# Y_Stepper_Motor_Driver.net
KiCad netlist of a schematic drawn in Altium Designer
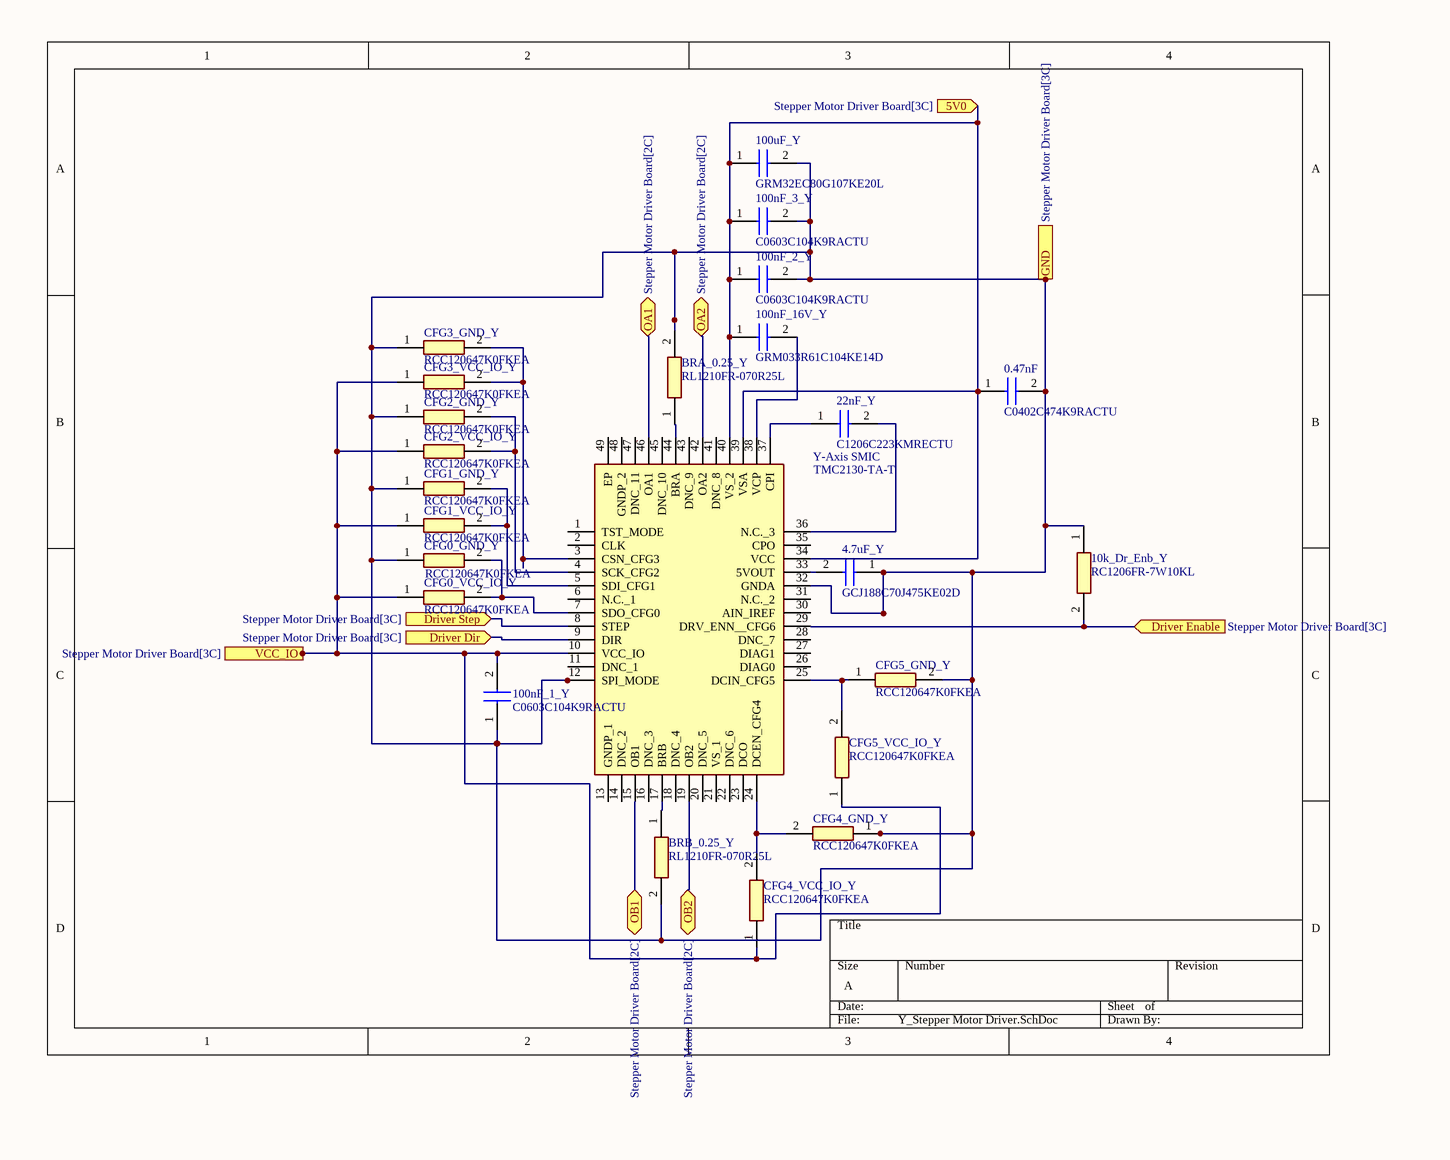
[diagram p0: Y_Stepper Motor Driver.SchDoc]

(export (version "E")
  (design (tool "Eeschema 10.0.6"))
  (components
    (comp (ref "0.47nF")
      (value "C0402C474K9RACTU")
      (footprint "SamacSys:CAPC1005X55N")
      (description "Capacitor")
      (fields (field (name "MOUSER PART NUMBER") "80-C0402C474K9RACTU"))
      (libsource (lib "*") (part "C0402C474K9RACTU"))
    )
    (comp (ref "4.7uF_Y")
      (value "GCJ188C70J475KE02D")
      (footprint "SamacSys:CAPC1608X100N")
      (description "Capacitor")
      (fields (field (name "MOUSER PART NUMBER") "81-GCJ188C70J475KE2D"))
      (libsource (lib "*") (part "GCJ188C70J475KE02D"))
    )
    (comp (ref "10k_Dr_Enb_Y")
      (value "RC1206FR-7W10KL")
      (footprint "SamacSys:RESC3116X65N")
      (description "Resistor")
      (libsource (lib "*") (part "RC1206FR-7W10KL"))
    )
    (comp (ref "22nF_Y")
      (value "C1206C223KMRECTU")
      (footprint "SamacSys:C1206")
      (description "Capacitor")
      (fields (field (name "MOUSER PART NUMBER") "80-C1206C223KMRECTU"))
      (libsource (lib "*") (part "C1206C223KMRECTU"))
    )
    (comp (ref "100nF_1_Y")
      (value "C0603C104K9RACTU")
      (footprint "SamacSys:C0603")
      (description "Capacitor")
      (fields (field (name "MOUSER PART NUMBER") "80-C0603C104K9R"))
      (libsource (lib "*") (part "C0603C104K9RACTU"))
    )
    (comp (ref "100nF_2_Y")
      (value "C0603C104K9RACTU")
      (footprint "SamacSys:C0603")
      (description "Capacitor")
      (fields (field (name "MOUSER PART NUMBER") "80-C0603C104K9R"))
      (libsource (lib "*") (part "C0603C104K9RACTU"))
    )
    (comp (ref "100nF_3_Y")
      (value "C0603C104K9RACTU")
      (footprint "SamacSys:C0603")
      (description "Capacitor")
      (fields (field (name "MOUSER PART NUMBER") "80-C0603C104K9R"))
      (libsource (lib "*") (part "C0603C104K9RACTU"))
    )
    (comp (ref "100nF_16V_Y")
      (value "GRM033R61C104KE14D")
      (footprint "SamacSys:CAPC0603X33N")
      (description "Capacitor")
      (fields (field (name "MOUSER PART NUMBER") "81-GRM033R61C104KE4D"))
      (libsource (lib "*") (part "GRM033R61C104KE14D"))
    )
    (comp (ref "100uF_Y")
      (value "GRM32EC80G107KE20L")
      (footprint "SamacSys:CAPC3225X270N")
      (description "Capacitor")
      (fields (field (name "MOUSER PART NUMBER") "81-GRM32EC80G107KE0L"))
      (libsource (lib "*") (part "GRM32EC80G107KE20L"))
    )
    (comp (ref "BRA_0.25_Y")
      (value "RL1210FR-070R25L")
      (footprint "SamacSys:RESC3126X65N")
      (description "Resistor")
      (fields (field (name "MOUSER PART NUMBER") "603-RL1210FR-070R25L"))
      (libsource (lib "*") (part "RL1210FR-070R25L"))
    )
    (comp (ref "BRB_0.25_Y")
      (value "RL1210FR-070R25L")
      (footprint "SamacSys:RESC3126X65N")
      (description "Resistor")
      (fields (field (name "MOUSER PART NUMBER") "603-RL1210FR-070R25L"))
      (libsource (lib "") (part "RL1210FR-070R25L_1"))
    )
    (comp (ref "CFG0_GND_Y")
      (value "RCC120647K0FKEA")
      (footprint "SamacSys:RCC1206_e3")
      (description "Resistor")
      (fields (field (name "MOUSER PART NUMBER") "71-RCC120647K0FKEA"))
      (libsource (lib "*") (part "RCC120647K0FKEA"))
    )
    (comp (ref "CFG0_VCC_IO_Y")
      (value "RCC120647K0FKEA")
      (footprint "SamacSys:RCC1206_e3")
      (description "Resistor")
      (fields (field (name "MOUSER PART NUMBER") "71-RCC120647K0FKEA"))
      (libsource (lib "*") (part "RCC120647K0FKEA"))
    )
    (comp (ref "CFG1_GND_Y")
      (value "RCC120647K0FKEA")
      (footprint "SamacSys:RCC1206_e3")
      (description "Resistor")
      (fields (field (name "MOUSER PART NUMBER") "71-RCC120647K0FKEA"))
      (libsource (lib "*") (part "RCC120647K0FKEA"))
    )
    (comp (ref "CFG1_VCC_IO_Y")
      (value "RCC120647K0FKEA")
      (footprint "SamacSys:RCC1206_e3")
      (description "Resistor")
      (fields (field (name "MOUSER PART NUMBER") "71-RCC120647K0FKEA"))
      (libsource (lib "*") (part "RCC120647K0FKEA"))
    )
    (comp (ref "CFG2_GND_Y")
      (value "RCC120647K0FKEA")
      (footprint "SamacSys:RCC1206_e3")
      (description "Resistor")
      (fields (field (name "MOUSER PART NUMBER") "71-RCC120647K0FKEA"))
      (libsource (lib "*") (part "RCC120647K0FKEA"))
    )
    (comp (ref "CFG2_VCC_IO_Y")
      (value "RCC120647K0FKEA")
      (footprint "SamacSys:RCC1206_e3")
      (description "Resistor")
      (fields (field (name "MOUSER PART NUMBER") "71-RCC120647K0FKEA"))
      (libsource (lib "*") (part "RCC120647K0FKEA"))
    )
    (comp (ref "CFG3_GND_Y")
      (value "RCC120647K0FKEA")
      (footprint "SamacSys:RCC1206_e3")
      (description "Resistor")
      (fields (field (name "MOUSER PART NUMBER") "71-RCC120647K0FKEA"))
      (libsource (lib "*") (part "RCC120647K0FKEA"))
    )
    (comp (ref "CFG3_VCC_IO_Y")
      (value "RCC120647K0FKEA")
      (footprint "SamacSys:RCC1206_e3")
      (description "Resistor")
      (fields (field (name "MOUSER PART NUMBER") "71-RCC120647K0FKEA"))
      (libsource (lib "*") (part "RCC120647K0FKEA"))
    )
    (comp (ref "CFG4_GND_Y")
      (value "RCC120647K0FKEA")
      (footprint "SamacSys:RCC1206_e3")
      (description "Resistor")
      (fields (field (name "MOUSER PART NUMBER") "71-RCC120647K0FKEA"))
      (libsource (lib "") (part "RCC120647K0FKEA_2"))
    )
    (comp (ref "CFG4_VCC_IO_Y")
      (value "RCC120647K0FKEA")
      (footprint "SamacSys:RCC1206_e3")
      (description "Resistor")
      (fields (field (name "MOUSER PART NUMBER") "71-RCC120647K0FKEA"))
      (libsource (lib "") (part "RCC120647K0FKEA_1"))
    )
    (comp (ref "CFG5_GND_Y")
      (value "RCC120647K0FKEA")
      (footprint "SamacSys:RCC1206_e3")
      (description "Resistor")
      (fields (field (name "MOUSER PART NUMBER") "71-RCC120647K0FKEA"))
      (libsource (lib "*") (part "RCC120647K0FKEA"))
    )
    (comp (ref "CFG5_VCC_IO_Y")
      (value "RCC120647K0FKEA")
      (footprint "SamacSys:RCC1206_e3")
      (description "Resistor")
      (fields (field (name "MOUSER PART NUMBER") "71-RCC120647K0FKEA"))
      (libsource (lib "") (part "RCC120647K0FKEA_1"))
    )
    (comp (ref "Y-Axis SMIC")
      (value "TMC2130-TA-T")
      (footprint "SamacSys:QFP50P900X900X120-49N")
      (description "Integrated Circuit")
      (fields (field (name "MOUSER PART NUMBER") "700-TMC2130-TA-T"))
      (libsource (lib "*") (part "TMC2130-TA-T"))
    )
  )
  (nets
    (net (code "1") (name "/5V0") (class "Default")
      (node (ref "0.47nF") (pin "1") (pinfunction "1_1") (pintype "passive"))
      (node (ref "100nF_16V_Y") (pin "1") (pinfunction "1_1") (pintype "passive"))
      (node (ref "100nF_2_Y") (pin "1") (pinfunction "1_1") (pintype "passive"))
      (node (ref "100nF_3_Y") (pin "1") (pinfunction "1_1") (pintype "passive"))
      (node (ref "100uF_Y") (pin "1") (pinfunction "1_1") (pintype "passive"))
      (node (ref "Y-Axis SMIC") (pin "34") (pinfunction "VCC_34") (pintype "passive"))
      (node (ref "Y-Axis SMIC") (pin "39") (pinfunction "VSA_39") (pintype "passive"))
      (node (ref "Y-Axis SMIC") (pin "40") (pinfunction "VS_2_40") (pintype "passive"))
    )
    (net (code "2") (name "/Driver Dir") (class "Default")
      (node (ref "Y-Axis SMIC") (pin "9") (pinfunction "DIR_9") (pintype "passive"))
    )
    (net (code "3") (name "/Driver Enable") (class "Default")
      (node (ref "10k_Dr_Enb_Y") (pin "2") (pinfunction "2_2") (pintype "passive"))
      (node (ref "Y-Axis SMIC") (pin "29") (pinfunction "DRV_ENN__CFG6_29") (pintype "passive"))
    )
    (net (code "4") (name "/Driver Step") (class "Default")
      (node (ref "Y-Axis SMIC") (pin "8") (pinfunction "STEP_8") (pintype "passive"))
    )
    (net (code "5") (name "/GND") (class "Default")
      (node (ref "0.47nF") (pin "2") (pinfunction "2_2") (pintype "passive"))
      (node (ref "100nF_1_Y") (pin "1") (pinfunction "1_1") (pintype "passive"))
      (node (ref "100nF_2_Y") (pin "2") (pinfunction "2_2") (pintype "passive"))
      (node (ref "100nF_3_Y") (pin "2") (pinfunction "2_2") (pintype "passive"))
      (node (ref "100uF_Y") (pin "2") (pinfunction "2_2") (pintype "passive"))
      (node (ref "10k_Dr_Enb_Y") (pin "1") (pinfunction "1_1") (pintype "passive"))
      (node (ref "4.7uF_Y") (pin "1") (pinfunction "1_1") (pintype "passive"))
      (node (ref "BRA_0.25_Y") (pin "2") (pinfunction "2_2") (pintype "passive"))
      (node (ref "BRB_0.25_Y") (pin "2") (pinfunction "2_2") (pintype "passive"))
      (node (ref "CFG0_GND_Y") (pin "1") (pinfunction "1_1") (pintype "passive"))
      (node (ref "CFG1_GND_Y") (pin "1") (pinfunction "1_1") (pintype "passive"))
      (node (ref "CFG2_GND_Y") (pin "1") (pinfunction "1_1") (pintype "passive"))
      (node (ref "CFG3_GND_Y") (pin "1") (pinfunction "1_1") (pintype "passive"))
      (node (ref "CFG4_GND_Y") (pin "1") (pinfunction "1_1") (pintype "passive"))
      (node (ref "CFG5_GND_Y") (pin "2") (pinfunction "2_2") (pintype "passive"))
      (node (ref "Y-Axis SMIC") (pin "12") (pinfunction "SPI_MODE_12") (pintype "passive"))
      (node (ref "Y-Axis SMIC") (pin "32") (pinfunction "GNDA_32") (pintype "passive"))
    )
    (net (code "6") (name "/OA1") (class "Default")
      (node (ref "Y-Axis SMIC") (pin "46") (pinfunction "OA1_46") (pintype "passive"))
    )
    (net (code "7") (name "/OA2") (class "Default")
      (node (ref "Y-Axis SMIC") (pin "42") (pinfunction "OA2_42") (pintype "passive"))
    )
    (net (code "8") (name "/OB1") (class "Default")
      (node (ref "Y-Axis SMIC") (pin "15") (pinfunction "OB1_15") (pintype "passive"))
    )
    (net (code "9") (name "/OB2") (class "Default")
      (node (ref "Y-Axis SMIC") (pin "19") (pinfunction "OB2_19") (pintype "passive"))
    )
    (net (code "10") (name "/VCC_IO") (class "Default")
      (node (ref "100nF_1_Y") (pin "2") (pinfunction "2_2") (pintype "passive"))
      (node (ref "CFG0_VCC_IO_Y") (pin "1") (pinfunction "1_1") (pintype "passive"))
      (node (ref "CFG1_VCC_IO_Y") (pin "1") (pinfunction "1_1") (pintype "passive"))
      (node (ref "CFG2_VCC_IO_Y") (pin "1") (pinfunction "1_1") (pintype "passive"))
      (node (ref "CFG3_VCC_IO_Y") (pin "1") (pinfunction "1_1") (pintype "passive"))
      (node (ref "CFG4_VCC_IO_Y") (pin "1") (pinfunction "1_1") (pintype "passive"))
      (node (ref "CFG5_VCC_IO_Y") (pin "1") (pinfunction "1_1") (pintype "passive"))
      (node (ref "Y-Axis SMIC") (pin "10") (pinfunction "VCC_IO_10") (pintype "passive"))
    )
    (net (code "11") (name "Net-(Y-Axis SMIC-5VOUT)") (class "Default")
      (node (ref "4.7uF_Y") (pin "2") (pinfunction "2_2") (pintype "passive"))
      (node (ref "Y-Axis SMIC") (pin "33") (pinfunction "5VOUT_33") (pintype "passive"))
    )
    (net (code "12") (name "Net-(Y-Axis SMIC-BRA)") (class "Default")
      (node (ref "BRA_0.25_Y") (pin "1") (pinfunction "1_1") (pintype "passive"))
      (node (ref "Y-Axis SMIC") (pin "44") (pinfunction "BRA_44") (pintype "passive"))
    )
    (net (code "13") (name "Net-(Y-Axis SMIC-BRB)") (class "Default")
      (node (ref "BRB_0.25_Y") (pin "1") (pinfunction "1_1") (pintype "passive"))
      (node (ref "Y-Axis SMIC") (pin "17") (pinfunction "BRB_17") (pintype "passive"))
    )
    (net (code "14") (name "Net-(Y-Axis SMIC-CPI)") (class "Default")
      (node (ref "22nF_Y") (pin "1") (pinfunction "1_1") (pintype "passive"))
      (node (ref "Y-Axis SMIC") (pin "37") (pinfunction "CPI_37") (pintype "passive"))
    )
    (net (code "15") (name "Net-(Y-Axis SMIC-CSN_CFG3)") (class "Default")
      (node (ref "CFG3_GND_Y") (pin "2") (pinfunction "2_2") (pintype "passive"))
      (node (ref "CFG3_VCC_IO_Y") (pin "2") (pinfunction "2_2") (pintype "passive"))
      (node (ref "Y-Axis SMIC") (pin "3") (pinfunction "CSN_CFG3_3") (pintype "passive"))
    )
    (net (code "16") (name "Net-(Y-Axis SMIC-DCEN_CFG4)") (class "Default")
      (node (ref "CFG4_GND_Y") (pin "2") (pinfunction "2_2") (pintype "passive"))
      (node (ref "CFG4_VCC_IO_Y") (pin "2") (pinfunction "2_2") (pintype "passive"))
      (node (ref "Y-Axis SMIC") (pin "24") (pinfunction "DCEN_CFG4_24") (pintype "passive"))
    )
    (net (code "17") (name "Net-(Y-Axis SMIC-DCIN_CFG5)") (class "Default")
      (node (ref "CFG5_GND_Y") (pin "1") (pinfunction "1_1") (pintype "passive"))
      (node (ref "CFG5_VCC_IO_Y") (pin "2") (pinfunction "2_2") (pintype "passive"))
      (node (ref "Y-Axis SMIC") (pin "25") (pinfunction "DCIN_CFG5_25") (pintype "passive"))
    )
    (net (code "18") (name "Net-(Y-Axis SMIC-N.C._3)") (class "Default")
      (node (ref "22nF_Y") (pin "2") (pinfunction "2_2") (pintype "passive"))
      (node (ref "Y-Axis SMIC") (pin "36") (pinfunction "N.C._3_36") (pintype "passive"))
    )
    (net (code "19") (name "Net-(Y-Axis SMIC-SCK_CFG2)") (class "Default")
      (node (ref "CFG2_GND_Y") (pin "2") (pinfunction "2_2") (pintype "passive"))
      (node (ref "CFG2_VCC_IO_Y") (pin "2") (pinfunction "2_2") (pintype "passive"))
      (node (ref "Y-Axis SMIC") (pin "4") (pinfunction "SCK_CFG2_4") (pintype "passive"))
    )
    (net (code "20") (name "Net-(Y-Axis SMIC-SDI_CFG1)") (class "Default")
      (node (ref "CFG1_GND_Y") (pin "2") (pinfunction "2_2") (pintype "passive"))
      (node (ref "CFG1_VCC_IO_Y") (pin "2") (pinfunction "2_2") (pintype "passive"))
      (node (ref "Y-Axis SMIC") (pin "5") (pinfunction "SDI_CFG1_5") (pintype "passive"))
    )
    (net (code "21") (name "Net-(Y-Axis SMIC-SDO_CFG0)") (class "Default")
      (node (ref "CFG0_GND_Y") (pin "2") (pinfunction "2_2") (pintype "passive"))
      (node (ref "CFG0_VCC_IO_Y") (pin "2") (pinfunction "2_2") (pintype "passive"))
      (node (ref "Y-Axis SMIC") (pin "7") (pinfunction "SDO_CFG0_7") (pintype "passive"))
    )
    (net (code "22") (name "Net-(Y-Axis SMIC-VCP)") (class "Default")
      (node (ref "100nF_16V_Y") (pin "2") (pinfunction "2_2") (pintype "passive"))
      (node (ref "Y-Axis SMIC") (pin "38") (pinfunction "VCP_38") (pintype "passive"))
    )
    (net (code "23") (name "unconnected-(Y-Axis SMIC-AIN_IREF-Pad30)") (class "Default")
      (node (ref "Y-Axis SMIC") (pin "30") (pinfunction "AIN_IREF_30") (pintype "passive"))
    )
    (net (code "24") (name "unconnected-(Y-Axis SMIC-CLK-Pad2)") (class "Default")
      (node (ref "Y-Axis SMIC") (pin "2") (pinfunction "CLK_2") (pintype "passive"))
    )
    (net (code "25") (name "unconnected-(Y-Axis SMIC-CPO-Pad35)") (class "Default")
      (node (ref "Y-Axis SMIC") (pin "35") (pinfunction "CPO_35") (pintype "passive"))
    )
    (net (code "26") (name "unconnected-(Y-Axis SMIC-DCO-Pad23)") (class "Default")
      (node (ref "Y-Axis SMIC") (pin "23") (pinfunction "DCO_23") (pintype "passive"))
    )
    (net (code "27") (name "unconnected-(Y-Axis SMIC-DIAG0-Pad26)") (class "Default")
      (node (ref "Y-Axis SMIC") (pin "26") (pinfunction "DIAG0_26") (pintype "passive"))
    )
    (net (code "28") (name "unconnected-(Y-Axis SMIC-DIAG1-Pad27)") (class "Default")
      (node (ref "Y-Axis SMIC") (pin "27") (pinfunction "DIAG1_27") (pintype "passive"))
    )
    (net (code "29") (name "unconnected-(Y-Axis SMIC-DNC_1-Pad11)") (class "Default")
      (node (ref "Y-Axis SMIC") (pin "11") (pinfunction "DNC_1_11") (pintype "passive"))
    )
    (net (code "30") (name "unconnected-(Y-Axis SMIC-DNC_2-Pad14)") (class "Default")
      (node (ref "Y-Axis SMIC") (pin "14") (pinfunction "DNC_2_14") (pintype "passive"))
    )
    (net (code "31") (name "unconnected-(Y-Axis SMIC-DNC_3-Pad16)") (class "Default")
      (node (ref "Y-Axis SMIC") (pin "16") (pinfunction "DNC_3_16") (pintype "passive"))
    )
    (net (code "32") (name "unconnected-(Y-Axis SMIC-DNC_4-Pad18)") (class "Default")
      (node (ref "Y-Axis SMIC") (pin "18") (pinfunction "DNC_4_18") (pintype "passive"))
    )
    (net (code "33") (name "unconnected-(Y-Axis SMIC-DNC_5-Pad20)") (class "Default")
      (node (ref "Y-Axis SMIC") (pin "20") (pinfunction "DNC_5_20") (pintype "passive"))
    )
    (net (code "34") (name "unconnected-(Y-Axis SMIC-DNC_6-Pad22)") (class "Default")
      (node (ref "Y-Axis SMIC") (pin "22") (pinfunction "DNC_6_22") (pintype "passive"))
    )
    (net (code "35") (name "unconnected-(Y-Axis SMIC-DNC_7-Pad28)") (class "Default")
      (node (ref "Y-Axis SMIC") (pin "28") (pinfunction "DNC_7_28") (pintype "passive"))
    )
    (net (code "36") (name "unconnected-(Y-Axis SMIC-DNC_8-Pad41)") (class "Default")
      (node (ref "Y-Axis SMIC") (pin "41") (pinfunction "DNC_8_41") (pintype "passive"))
    )
    (net (code "37") (name "unconnected-(Y-Axis SMIC-DNC_9-Pad43)") (class "Default")
      (node (ref "Y-Axis SMIC") (pin "43") (pinfunction "DNC_9_43") (pintype "passive"))
    )
    (net (code "38") (name "unconnected-(Y-Axis SMIC-DNC_10-Pad45)") (class "Default")
      (node (ref "Y-Axis SMIC") (pin "45") (pinfunction "DNC_10_45") (pintype "passive"))
    )
    (net (code "39") (name "unconnected-(Y-Axis SMIC-DNC_11-Pad47)") (class "Default")
      (node (ref "Y-Axis SMIC") (pin "47") (pinfunction "DNC_11_47") (pintype "passive"))
    )
    (net (code "40") (name "unconnected-(Y-Axis SMIC-EP-Pad49)") (class "Default")
      (node (ref "Y-Axis SMIC") (pin "49") (pinfunction "EP_49") (pintype "passive"))
    )
    (net (code "41") (name "unconnected-(Y-Axis SMIC-GNDP_1-Pad13)") (class "Default")
      (node (ref "Y-Axis SMIC") (pin "13") (pinfunction "GNDP_1_13") (pintype "passive"))
    )
    (net (code "42") (name "unconnected-(Y-Axis SMIC-GNDP_2-Pad48)") (class "Default")
      (node (ref "Y-Axis SMIC") (pin "48") (pinfunction "GNDP_2_48") (pintype "passive"))
    )
    (net (code "43") (name "unconnected-(Y-Axis SMIC-N.C._1-Pad6)") (class "Default")
      (node (ref "Y-Axis SMIC") (pin "6") (pinfunction "N.C._1_6") (pintype "passive"))
    )
    (net (code "44") (name "unconnected-(Y-Axis SMIC-N.C._2-Pad31)") (class "Default")
      (node (ref "Y-Axis SMIC") (pin "31") (pinfunction "N.C._2_31") (pintype "passive"))
    )
    (net (code "45") (name "unconnected-(Y-Axis SMIC-TST_MODE-Pad1)") (class "Default")
      (node (ref "Y-Axis SMIC") (pin "1") (pinfunction "TST_MODE_1") (pintype "passive"))
    )
    (net (code "46") (name "unconnected-(Y-Axis SMIC-VS_1-Pad21)") (class "Default")
      (node (ref "Y-Axis SMIC") (pin "21") (pinfunction "VS_1_21") (pintype "passive"))
    )
  )
)
